# untitled.net
KiCad netlist of a schematic drawn in EAGLE
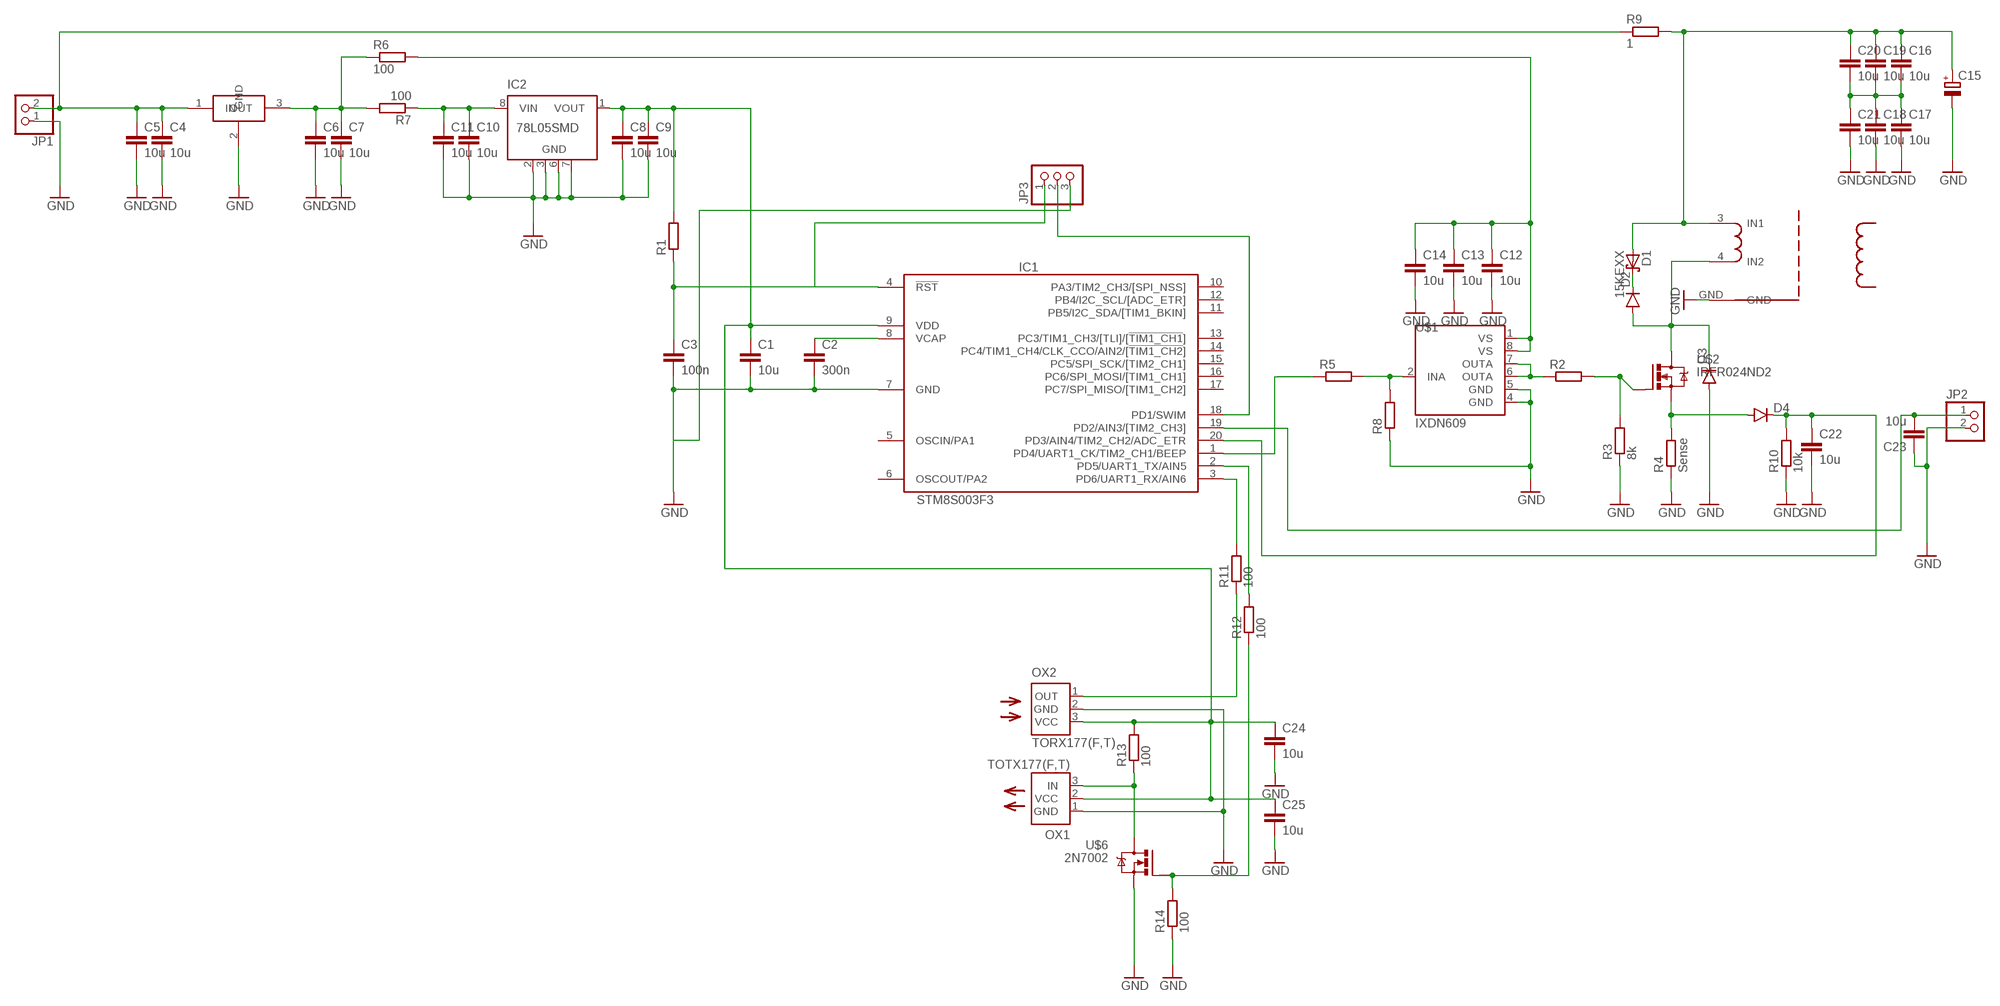
[diagram p0: schematic, sheet 1]

(export (version "E")
  (design (tool "Eeschema 10.0.6"))
  (components
    (comp (ref "C1")
      (value "10u")
      (footprint "eagle-import:C0805")
      (libsource (lib "eagle-import") (part "CC0805"))
    )
    (comp (ref "C2")
      (value "300n")
      (footprint "eagle-import:C0805")
      (libsource (lib "eagle-import") (part "CC0805"))
    )
    (comp (ref "C3")
      (value "100n")
      (footprint "eagle-import:C0805")
      (libsource (lib "eagle-import") (part "CC0805"))
    )
    (comp (ref "C4")
      (value "10u")
      (footprint "eagle-import:C0805")
      (libsource (lib "eagle-import") (part "CC0805"))
    )
    (comp (ref "C5")
      (value "10u")
      (footprint "eagle-import:C0805")
      (libsource (lib "eagle-import") (part "CC0805"))
    )
    (comp (ref "C6")
      (value "10u")
      (footprint "eagle-import:C0805")
      (libsource (lib "eagle-import") (part "CC0805"))
    )
    (comp (ref "C7")
      (value "10u")
      (footprint "eagle-import:C0805")
      (libsource (lib "eagle-import") (part "CC0805"))
    )
    (comp (ref "C8")
      (value "10u")
      (footprint "eagle-import:C0805")
      (libsource (lib "eagle-import") (part "CC0805"))
    )
    (comp (ref "C9")
      (value "10u")
      (footprint "eagle-import:C0805")
      (libsource (lib "eagle-import") (part "CC0805"))
    )
    (comp (ref "C10")
      (value "10u")
      (footprint "eagle-import:C0805")
      (libsource (lib "eagle-import") (part "CC0805"))
    )
    (comp (ref "C11")
      (value "10u")
      (footprint "eagle-import:C0805")
      (libsource (lib "eagle-import") (part "CC0805"))
    )
    (comp (ref "C12")
      (value "10u")
      (footprint "eagle-import:C0805")
      (libsource (lib "eagle-import") (part "CC0805"))
    )
    (comp (ref "C13")
      (value "10u")
      (footprint "eagle-import:C0805")
      (libsource (lib "eagle-import") (part "CC0805"))
    )
    (comp (ref "C14")
      (value "10u")
      (footprint "eagle-import:C0805")
      (libsource (lib "eagle-import") (part "CC0805"))
    )
    (comp (ref "C15")
      (value "CPOL-EUE7.5-16")
      (footprint "eagle-import:E7,5-16")
      (libsource (lib "eagle-import") (part "CPOL-EUE7.5-16"))
    )
    (comp (ref "C16")
      (value "10u")
      (footprint "eagle-import:C0805")
      (libsource (lib "eagle-import") (part "CC0805"))
    )
    (comp (ref "C17")
      (value "10u")
      (footprint "eagle-import:C0805")
      (libsource (lib "eagle-import") (part "CC0805"))
    )
    (comp (ref "C18")
      (value "10u")
      (footprint "eagle-import:C0805")
      (libsource (lib "eagle-import") (part "CC0805"))
    )
    (comp (ref "C19")
      (value "10u")
      (footprint "eagle-import:C0805")
      (libsource (lib "eagle-import") (part "CC0805"))
    )
    (comp (ref "C20")
      (value "10u")
      (footprint "eagle-import:C0805")
      (libsource (lib "eagle-import") (part "CC0805"))
    )
    (comp (ref "C21")
      (value "10u")
      (footprint "eagle-import:C0805")
      (libsource (lib "eagle-import") (part "CC0805"))
    )
    (comp (ref "C22")
      (value "10u")
      (footprint "eagle-import:C0805")
      (libsource (lib "eagle-import") (part "CC0805"))
    )
    (comp (ref "C23")
      (value "10u")
      (footprint "eagle-import:C0805")
      (libsource (lib "eagle-import") (part "CC0805"))
    )
    (comp (ref "C24")
      (value "10u")
      (footprint "eagle-import:C0805")
      (libsource (lib "eagle-import") (part "CC0805"))
    )
    (comp (ref "C25")
      (value "10u")
      (footprint "eagle-import:C0805")
      (libsource (lib "eagle-import") (part "CC0805"))
    )
    (comp (ref "D1")
      (value "15KEXX")
      (footprint "eagle-import:CB429-17")
      (libsource (lib "eagle-import") (part "15KEXX"))
    )
    (comp (ref "D2")
      (value "DIODESMA")
      (footprint "eagle-import:SMA-DIODE")
      (libsource (lib "eagle-import") (part "DIODESMA"))
    )
    (comp (ref "D3")
      (value "DIODESMA")
      (footprint "eagle-import:SMA-DIODE")
      (libsource (lib "eagle-import") (part "DIODESMA"))
    )
    (comp (ref "D4")
      (value "DIODESOD123")
      (footprint "eagle-import:SOD-123")
      (libsource (lib "eagle-import") (part "DIODESOD123"))
    )
    (comp (ref "IC1")
      (value "STM8S003F3")
      (footprint "eagle-import:TSSOP20")
      (libsource (lib "eagle-import") (part "STM8S003F3"))
    )
    (comp (ref "IC2")
      (value "78L05SMD")
      (footprint "eagle-import:SO08")
      (libsource (lib "eagle-import") (part "78LSMD05"))
    )
    (comp (ref "JP1")
      (value "PINHD-1X2")
      (footprint "eagle-import:1X02")
      (libsource (lib "eagle-import") (part "PINHD-1X2"))
    )
    (comp (ref "JP2")
      (value "PINHD-1X2")
      (footprint "eagle-import:1X02")
      (libsource (lib "eagle-import") (part "PINHD-1X2"))
    )
    (comp (ref "JP3")
      (value "PINHD-1X3")
      (footprint "eagle-import:1X03")
      (libsource (lib "eagle-import") (part "PINHD-1X3"))
    )
    (comp (ref "OX1")
      (value "TOTX177(F,T)")
      (footprint "eagle-import:TOTX")
      (libsource (lib "eagle-import") (part "TOTX177(F,T)"))
    )
    (comp (ref "OX2")
      (value "TORX177(F,T)")
      (footprint "eagle-import:TORX")
      (libsource (lib "eagle-import") (part "TORX177(F,T)"))
    )
    (comp (ref "R1")
      (value "R0603")
      (footprint "eagle-import:0603")
      (libsource (lib "eagle-import") (part "R0603"))
    )
    (comp (ref "R2")
      (value "R0805")
      (footprint "eagle-import:R0805")
      (libsource (lib "eagle-import") (part "R0805"))
    )
    (comp (ref "R3")
      (value "8k")
      (footprint "eagle-import:R0805")
      (libsource (lib "eagle-import") (part "R0805"))
    )
    (comp (ref "R4")
      (value "Sense")
      (footprint "eagle-import:R2512")
      (libsource (lib "eagle-import") (part "RR2512"))
    )
    (comp (ref "R5")
      (value "R0805")
      (footprint "eagle-import:R0805")
      (libsource (lib "eagle-import") (part "R0805"))
    )
    (comp (ref "R6")
      (value "100")
      (footprint "eagle-import:R0805")
      (libsource (lib "eagle-import") (part "R0805"))
    )
    (comp (ref "R7")
      (value "100")
      (footprint "eagle-import:R0805")
      (libsource (lib "eagle-import") (part "R0805"))
    )
    (comp (ref "R8")
      (value "R0805")
      (footprint "eagle-import:R0805")
      (libsource (lib "eagle-import") (part "R0805"))
    )
    (comp (ref "R9")
      (value "1")
      (footprint "eagle-import:R1206")
      (libsource (lib "eagle-import") (part "R1206"))
    )
    (comp (ref "R10")
      (value "10k")
      (footprint "eagle-import:R0805")
      (libsource (lib "eagle-import") (part "R0805"))
    )
    (comp (ref "R11")
      (value "100")
      (footprint "eagle-import:0603")
      (libsource (lib "eagle-import") (part "R0603"))
    )
    (comp (ref "R12")
      (value "100")
      (footprint "eagle-import:0603")
      (libsource (lib "eagle-import") (part "R0603"))
    )
    (comp (ref "R13")
      (value "100")
      (footprint "eagle-import:0603")
      (libsource (lib "eagle-import") (part "R0603"))
    )
    (comp (ref "R14")
      (value "100")
      (footprint "eagle-import:0603")
      (libsource (lib "eagle-import") (part "R0603"))
    )
    (comp (ref "U$1")
      (value "IXDN609")
      (footprint "eagle-import:SO08")
      (libsource (lib "eagle-import") (part "IXDN609"))
    )
    (comp (ref "U$2")
      (value "IRFR024ND2")
      (footprint "eagle-import:D2PACK")
      (libsource (lib "eagle-import") (part "IRFR024ND2"))
    )
    (comp (ref "U$3")
      (value "TVS-90P6")
      (footprint "eagle-import:TVS-90P6")
      (libsource (lib "eagle-import") (part "TVS-90P6"))
    )
    (comp (ref "U$4")
      (value "L7805C2T")
      (footprint "eagle-import:D2PACK")
      (libsource (lib "eagle-import") (part "L7805C2T"))
    )
    (comp (ref "U$6")
      (value "2N7002")
      (footprint "eagle-import:SOT23")
      (libsource (lib "eagle-import") (part "2N7002"))
    )
  )
  (nets
    (net (code "1") (name "GND") (class "Default")
      (node (ref "C1") (pin "2") (pinfunction "2_2") (pintype "passive"))
      (node (ref "C10") (pin "2") (pinfunction "2_2") (pintype "passive"))
      (node (ref "C11") (pin "2") (pinfunction "2_2") (pintype "passive"))
      (node (ref "C12") (pin "2") (pinfunction "2_2") (pintype "passive"))
      (node (ref "C13") (pin "2") (pinfunction "2_2") (pintype "passive"))
      (node (ref "C14") (pin "2") (pinfunction "2_2") (pintype "passive"))
      (node (ref "C15") (pin "-") (pinfunction "-_-") (pintype "passive"))
      (node (ref "C17") (pin "2") (pinfunction "2_2") (pintype "passive"))
      (node (ref "C18") (pin "2") (pinfunction "2_2") (pintype "passive"))
      (node (ref "C2") (pin "2") (pinfunction "2_2") (pintype "passive"))
      (node (ref "C21") (pin "2") (pinfunction "2_2") (pintype "passive"))
      (node (ref "C22") (pin "2") (pinfunction "2_2") (pintype "passive"))
      (node (ref "C23") (pin "1") (pinfunction "1_1") (pintype "passive"))
      (node (ref "C24") (pin "2") (pinfunction "2_2") (pintype "passive"))
      (node (ref "C25") (pin "2") (pinfunction "2_2") (pintype "passive"))
      (node (ref "C3") (pin "2") (pinfunction "2_2") (pintype "passive"))
      (node (ref "C4") (pin "2") (pinfunction "2_2") (pintype "passive"))
      (node (ref "C5") (pin "2") (pinfunction "2_2") (pintype "passive"))
      (node (ref "C6") (pin "2") (pinfunction "2_2") (pintype "passive"))
      (node (ref "C7") (pin "2") (pinfunction "2_2") (pintype "passive"))
      (node (ref "C8") (pin "2") (pinfunction "2_2") (pintype "passive"))
      (node (ref "C9") (pin "2") (pinfunction "2_2") (pintype "passive"))
      (node (ref "D3") (pin "A") (pinfunction "A_A") (pintype "passive"))
      (node (ref "IC1") (pin "7") (pinfunction "GND_7") (pintype "power_in"))
      (node (ref "IC2") (pin "2") (pinfunction "GND_2") (pintype "power_in"))
      (node (ref "IC2") (pin "3") (pinfunction "GND_3") (pintype "power_in"))
      (node (ref "IC2") (pin "6") (pinfunction "GND_6") (pintype "power_in"))
      (node (ref "IC2") (pin "7") (pinfunction "GND_7") (pintype "power_in"))
      (node (ref "JP1") (pin "1") (pinfunction "1_1") (pintype "passive"))
      (node (ref "JP2") (pin "2") (pinfunction "2_2") (pintype "passive"))
      (node (ref "JP3") (pin "3") (pinfunction "3_3") (pintype "passive"))
      (node (ref "OX1") (pin "1") (pinfunction "GND_1") (pintype "power_in"))
      (node (ref "OX2") (pin "2") (pinfunction "GND_2") (pintype "power_in"))
      (node (ref "R10") (pin "1") (pinfunction "1_1") (pintype "passive"))
      (node (ref "R14") (pin "1") (pinfunction "1_1") (pintype "passive"))
      (node (ref "R3") (pin "1") (pinfunction "1_1") (pintype "passive"))
      (node (ref "R4") (pin "1") (pinfunction "1_1") (pintype "passive"))
      (node (ref "R8") (pin "1") (pinfunction "1_1") (pintype "passive"))
      (node (ref "U$1") (pin "4") (pinfunction "GND_4") (pintype "power_in"))
      (node (ref "U$1") (pin "5") (pinfunction "GND_5") (pintype "power_in"))
      (node (ref "U$3") (pin "GND") (pinfunction "GND_GND") (pintype "bidirectional"))
      (node (ref "U$4") (pin "2") (pinfunction "GND_2") (pintype "bidirectional"))
      (node (ref "U$6") (pin "2") (pinfunction "S_2") (pintype "passive"))
    )
    (net (code "2") (name "Net-(C12-Pad1)") (class "Default")
      (node (ref "C12") (pin "1") (pinfunction "1_1") (pintype "passive"))
      (node (ref "C13") (pin "1") (pinfunction "1_1") (pintype "passive"))
      (node (ref "C14") (pin "1") (pinfunction "1_1") (pintype "passive"))
      (node (ref "R6") (pin "2") (pinfunction "2_2") (pintype "passive"))
      (node (ref "U$1") (pin "1") (pinfunction "VS_1") (pintype "power_in"))
      (node (ref "U$1") (pin "8") (pinfunction "VS_8") (pintype "power_in"))
    )
    (net (code "3") (name "Net-(C16-Pad2)") (class "Default")
      (node (ref "C16") (pin "2") (pinfunction "2_2") (pintype "passive"))
      (node (ref "C17") (pin "1") (pinfunction "1_1") (pintype "passive"))
      (node (ref "C18") (pin "1") (pinfunction "1_1") (pintype "passive"))
      (node (ref "C19") (pin "2") (pinfunction "2_2") (pintype "passive"))
      (node (ref "C20") (pin "2") (pinfunction "2_2") (pintype "passive"))
      (node (ref "C21") (pin "1") (pinfunction "1_1") (pintype "passive"))
    )
    (net (code "4") (name "Net-(D1-PadC)") (class "Default")
      (node (ref "D1") (pin "C") (pinfunction "C_C") (pintype "passive"))
      (node (ref "D2") (pin "C") (pinfunction "C_C") (pintype "passive"))
    )
    (net (code "5") (name "Net-(IC1-PD1{slash}SWIM)") (class "Default")
      (node (ref "IC1") (pin "18") (pinfunction "PD1/SWIM_18") (pintype "bidirectional"))
      (node (ref "JP3") (pin "2") (pinfunction "2_2") (pintype "passive"))
    )
    (net (code "6") (name "Net-(IC1-PD2{slash}AIN3{slash}[TIM2_CH3])") (class "Default")
      (node (ref "C23") (pin "2") (pinfunction "2_2") (pintype "passive"))
      (node (ref "IC1") (pin "19") (pinfunction "PD2/AIN3/[TIM2_CH3]_19") (pintype "bidirectional"))
      (node (ref "JP2") (pin "1") (pinfunction "1_1") (pintype "passive"))
    )
    (net (code "7") (name "Net-(IC1-PD3{slash}AIN4{slash}TIM2_CH2{slash}ADC_ETR)") (class "Default")
      (node (ref "C22") (pin "1") (pinfunction "1_1") (pintype "passive"))
      (node (ref "D4") (pin "C") (pinfunction "C_C") (pintype "passive"))
      (node (ref "IC1") (pin "20") (pinfunction "PD3/AIN4/TIM2_CH2/ADC_ETR_20") (pintype "bidirectional"))
      (node (ref "R10") (pin "2") (pinfunction "2_2") (pintype "passive"))
    )
    (net (code "8") (name "Net-(IC1-PD4{slash}UART1_CK{slash}TIM2_CH1{slash}BEEP)") (class "Default")
      (node (ref "IC1") (pin "1") (pinfunction "PD4/UART1_CK/TIM2_CH1/BEEP_1") (pintype "bidirectional"))
      (node (ref "R5") (pin "1") (pinfunction "1_1") (pintype "passive"))
    )
    (net (code "9") (name "Net-(IC1-PD5{slash}UART1_TX{slash}AIN5)") (class "Default")
      (node (ref "IC1") (pin "2") (pinfunction "PD5/UART1_TX/AIN5_2") (pintype "bidirectional"))
      (node (ref "R12") (pin "2") (pinfunction "2_2") (pintype "passive"))
    )
    (net (code "10") (name "Net-(IC1-PD6{slash}UART1_RX{slash}AIN6)") (class "Default")
      (node (ref "IC1") (pin "3") (pinfunction "PD6/UART1_RX/AIN6_3") (pintype "bidirectional"))
      (node (ref "R11") (pin "2") (pinfunction "2_2") (pintype "passive"))
    )
    (net (code "11") (name "Net-(IC1-VCAP)") (class "Default")
      (node (ref "C2") (pin "1") (pinfunction "1_1") (pintype "passive"))
      (node (ref "IC1") (pin "8") (pinfunction "VCAP_8") (pintype "power_in"))
    )
    (net (code "12") (name "Net-(IC1-VDD)") (class "Default")
      (node (ref "C1") (pin "1") (pinfunction "1_1") (pintype "passive"))
      (node (ref "C24") (pin "1") (pinfunction "1_1") (pintype "passive"))
      (node (ref "C25") (pin "1") (pinfunction "1_1") (pintype "passive"))
      (node (ref "C8") (pin "1") (pinfunction "1_1") (pintype "passive"))
      (node (ref "C9") (pin "1") (pinfunction "1_1") (pintype "passive"))
      (node (ref "IC1") (pin "9") (pinfunction "VDD_9") (pintype "power_in"))
      (node (ref "IC2") (pin "1") (pinfunction "VOUT_1") (pintype "output"))
      (node (ref "OX1") (pin "2") (pinfunction "VCC_2") (pintype "power_in"))
      (node (ref "OX2") (pin "3") (pinfunction "VCC_3") (pintype "power_in"))
      (node (ref "R1") (pin "2") (pinfunction "2_2") (pintype "passive"))
      (node (ref "R13") (pin "2") (pinfunction "2_2") (pintype "passive"))
    )
    (net (code "13") (name "Net-(IC1-~{RST})") (class "Default")
      (node (ref "C3") (pin "1") (pinfunction "1_1") (pintype "passive"))
      (node (ref "IC1") (pin "4") (pinfunction "~{RST}_4") (pintype "input"))
      (node (ref "JP3") (pin "1") (pinfunction "1_1") (pintype "passive"))
      (node (ref "R1") (pin "1") (pinfunction "1_1") (pintype "passive"))
    )
    (net (code "14") (name "Net-(IC2A-VIN)") (class "Default")
      (node (ref "C10") (pin "1") (pinfunction "1_1") (pintype "passive"))
      (node (ref "C11") (pin "1") (pinfunction "1_1") (pintype "passive"))
      (node (ref "IC2") (pin "8") (pinfunction "VIN_8") (pintype "passive"))
      (node (ref "R7") (pin "1") (pinfunction "1_1") (pintype "passive"))
    )
    (net (code "15") (name "Net-(OX1-IN)") (class "Default")
      (node (ref "OX1") (pin "3") (pinfunction "IN_3") (pintype "input"))
      (node (ref "R13") (pin "1") (pinfunction "1_1") (pintype "passive"))
      (node (ref "U$6") (pin "3") (pinfunction "D_3") (pintype "passive"))
    )
    (net (code "16") (name "Net-(OX2-OUT)") (class "Default")
      (node (ref "OX2") (pin "1") (pinfunction "OUT_1") (pintype "output"))
      (node (ref "R11") (pin "1") (pinfunction "1_1") (pintype "passive"))
    )
    (net (code "17") (name "Net-(R2-Pad1)") (class "Default")
      (node (ref "R2") (pin "1") (pinfunction "1_1") (pintype "passive"))
      (node (ref "U$1") (pin "6") (pinfunction "OUTA_6") (pintype "output"))
      (node (ref "U$1") (pin "7") (pinfunction "OUTA_7") (pintype "output"))
    )
    (net (code "18") (name "Net-(U$1-INA)") (class "Default")
      (node (ref "R5") (pin "2") (pinfunction "2_2") (pintype "passive"))
      (node (ref "R8") (pin "2") (pinfunction "2_2") (pintype "passive"))
      (node (ref "U$1") (pin "2") (pinfunction "INA_2") (pintype "input"))
    )
    (net (code "19") (name "Net-(U$2-D)") (class "Default")
      (node (ref "D2") (pin "A") (pinfunction "A_A") (pintype "passive"))
      (node (ref "D3") (pin "C") (pinfunction "C_C") (pintype "passive"))
      (node (ref "U$2") (pin "2") (pinfunction "D_2") (pintype "passive"))
      (node (ref "U$3") (pin "4") (pinfunction "IN2_4") (pintype "bidirectional"))
    )
    (net (code "20") (name "Net-(U$2-G)") (class "Default")
      (node (ref "R2") (pin "2") (pinfunction "2_2") (pintype "passive"))
      (node (ref "R3") (pin "2") (pinfunction "2_2") (pintype "passive"))
      (node (ref "U$2") (pin "1") (pinfunction "G_1") (pintype "passive"))
    )
    (net (code "21") (name "Net-(U$2-S)") (class "Default")
      (node (ref "D4") (pin "A") (pinfunction "A_A") (pintype "passive"))
      (node (ref "R4") (pin "2") (pinfunction "2_2") (pintype "passive"))
      (node (ref "U$2") (pin "3") (pinfunction "S_3") (pintype "passive"))
    )
    (net (code "22") (name "Net-(U$3-IN1)") (class "Default")
      (node (ref "C15") (pin "+") (pinfunction "+_+") (pintype "passive"))
      (node (ref "C16") (pin "1") (pinfunction "1_1") (pintype "passive"))
      (node (ref "C19") (pin "1") (pinfunction "1_1") (pintype "passive"))
      (node (ref "C20") (pin "1") (pinfunction "1_1") (pintype "passive"))
      (node (ref "D1") (pin "A") (pinfunction "A_A") (pintype "passive"))
      (node (ref "R9") (pin "2") (pinfunction "2_2") (pintype "passive"))
      (node (ref "U$3") (pin "3") (pinfunction "IN1_3") (pintype "bidirectional"))
    )
    (net (code "23") (name "Net-(U$4-IN)") (class "Default")
      (node (ref "C4") (pin "1") (pinfunction "1_1") (pintype "passive"))
      (node (ref "C5") (pin "1") (pinfunction "1_1") (pintype "passive"))
      (node (ref "JP1") (pin "2") (pinfunction "2_2") (pintype "passive"))
      (node (ref "R9") (pin "1") (pinfunction "1_1") (pintype "passive"))
      (node (ref "U$4") (pin "1") (pinfunction "IN_1") (pintype "bidirectional"))
    )
    (net (code "24") (name "Net-(U$4-OUT)") (class "Default")
      (node (ref "C6") (pin "1") (pinfunction "1_1") (pintype "passive"))
      (node (ref "C7") (pin "1") (pinfunction "1_1") (pintype "passive"))
      (node (ref "R6") (pin "1") (pinfunction "1_1") (pintype "passive"))
      (node (ref "R7") (pin "2") (pinfunction "2_2") (pintype "passive"))
      (node (ref "U$4") (pin "3") (pinfunction "OUT_3") (pintype "bidirectional"))
    )
    (net (code "25") (name "Net-(U$6-G)") (class "Default")
      (node (ref "R12") (pin "1") (pinfunction "1_1") (pintype "passive"))
      (node (ref "R14") (pin "2") (pinfunction "2_2") (pintype "passive"))
      (node (ref "U$6") (pin "1") (pinfunction "G_1") (pintype "passive"))
    )
    (net (code "26") (name "unconnected-(IC1-OSCIN{slash}PA1-Pad5)") (class "Default")
      (node (ref "IC1") (pin "5") (pinfunction "OSCIN/PA1_5") (pintype "bidirectional"))
    )
    (net (code "27") (name "unconnected-(IC1-OSCOUT{slash}PA2-Pad6)") (class "Default")
      (node (ref "IC1") (pin "6") (pinfunction "OSCOUT/PA2_6") (pintype "bidirectional"))
    )
    (net (code "28") (name "unconnected-(IC1-PA3{slash}TIM2_CH3{slash}[SPI_NSS]-Pad10)") (class "Default")
      (node (ref "IC1") (pin "10") (pinfunction "PA3/TIM2_CH3/[SPI_NSS]_10") (pintype "bidirectional"))
    )
    (net (code "29") (name "unconnected-(IC1-PB4{slash}I2C_SCL{slash}[ADC_ETR]-Pad12)") (class "Default")
      (node (ref "IC1") (pin "12") (pinfunction "PB4/I2C_SCL/[ADC_ETR]_12") (pintype "bidirectional"))
    )
    (net (code "30") (name "unconnected-(IC1-PB5{slash}I2C_SDA{slash}[TIM1_BKIN]-Pad11)") (class "Default")
      (node (ref "IC1") (pin "11") (pinfunction "PB5/I2C_SDA/[TIM1_BKIN]_11") (pintype "bidirectional"))
    )
    (net (code "31") (name "unconnected-(IC1-PC3{slash}TIM1_CH3{slash}[TLI]{slash}[~{TIM1_CH1}]-Pad13)") (class "Default")
      (node (ref "IC1") (pin "13") (pinfunction "PC3/TIM1_CH3/[TLI]/[~{TIM1_CH1}]_13") (pintype "bidirectional"))
    )
    (net (code "32") (name "unconnected-(IC1-PC4{slash}TIM1_CH4{slash}CLK_CCO{slash}AIN2{slash}[~{TIM1_CH2}]-Pad14)") (class "Default")
      (node (ref "IC1") (pin "14") (pinfunction "PC4/TIM1_CH4/CLK_CCO/AIN2/[~{TIM1_CH2}]_14") (pintype "bidirectional"))
    )
    (net (code "33") (name "unconnected-(IC1-PC5{slash}SPI_SCK{slash}[TIM2_CH1]-Pad15)") (class "Default")
      (node (ref "IC1") (pin "15") (pinfunction "PC5/SPI_SCK/[TIM2_CH1]_15") (pintype "bidirectional"))
    )
    (net (code "34") (name "unconnected-(IC1-PC6{slash}SPI_MOSI{slash}[TIM1_CH1]-Pad16)") (class "Default")
      (node (ref "IC1") (pin "16") (pinfunction "PC6/SPI_MOSI/[TIM1_CH1]_16") (pintype "bidirectional"))
    )
    (net (code "35") (name "unconnected-(IC1-PC7{slash}SPI_MISO{slash}[TIM1_CH2]-Pad17)") (class "Default")
      (node (ref "IC1") (pin "17") (pinfunction "PC7/SPI_MISO/[TIM1_CH2]_17") (pintype "bidirectional"))
    )
  )
)
